# Register.net
KiCad netlist of a schematic drawn in EAGLE
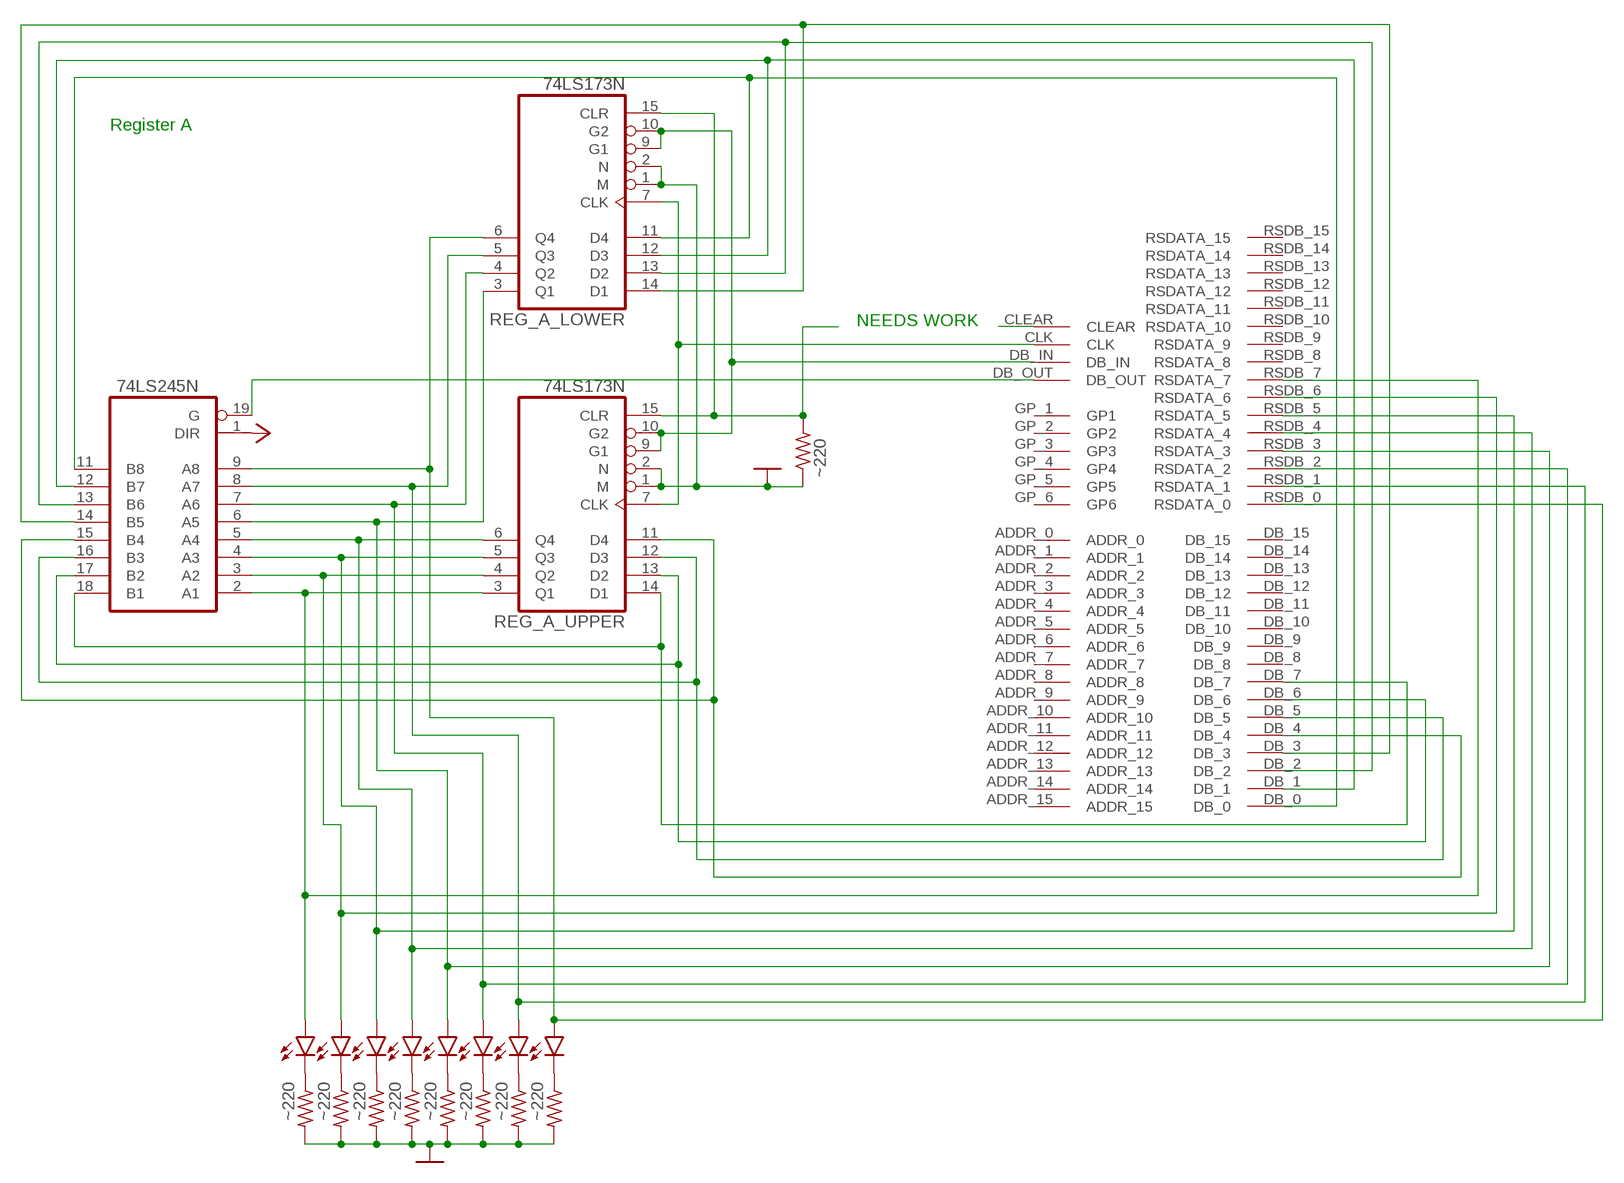
[diagram p0: schematic, sheet 1]

(export (version "E")
  (design (tool "Eeschema 10.0.6"))
  (components
    (comp (ref "LED_A_REG_1")
      (value "LED")
      (footprint "eagle-import:LED5MM")
      (libsource (lib "eagle-import") (part "LED5MM"))
    )
    (comp (ref "LED_A_REG_2")
      (value "LED")
      (footprint "eagle-import:LED5MM")
      (libsource (lib "eagle-import") (part "LED5MM"))
    )
    (comp (ref "LED_A_REG_3")
      (value "LED")
      (footprint "eagle-import:LED5MM")
      (libsource (lib "eagle-import") (part "LED5MM"))
    )
    (comp (ref "LED_A_REG_4")
      (value "LED")
      (footprint "eagle-import:LED5MM")
      (libsource (lib "eagle-import") (part "LED5MM"))
    )
    (comp (ref "LED_A_REG_5")
      (value "LED")
      (footprint "eagle-import:LED5MM")
      (libsource (lib "eagle-import") (part "LED5MM"))
    )
    (comp (ref "LED_A_REG_6")
      (value "LED")
      (footprint "eagle-import:LED5MM")
      (libsource (lib "eagle-import") (part "LED5MM"))
    )
    (comp (ref "LED_A_REG_7")
      (value "LED")
      (footprint "eagle-import:LED5MM")
      (libsource (lib "eagle-import") (part "LED5MM"))
    )
    (comp (ref "LED_A_REG_8")
      (value "LED")
      (footprint "eagle-import:LED5MM")
      (libsource (lib "eagle-import") (part "LED5MM"))
    )
    (comp (ref "OUTPUT_BUFFER_REG_A")
      (value "74LS245N")
      (footprint "eagle-import:DIL20")
      (libsource (lib "eagle-import") (part "74245NLS"))
    )
    (comp (ref "R1")
      (value "~220")
      (footprint "eagle-import:0204_7")
      (libsource (lib "eagle-import") (part "R-US_0204/7"))
    )
    (comp (ref "R2")
      (value "~220")
      (footprint "eagle-import:0204_7")
      (libsource (lib "eagle-import") (part "R-US_0204/7"))
    )
    (comp (ref "R3")
      (value "~220")
      (footprint "eagle-import:0204_7")
      (libsource (lib "eagle-import") (part "R-US_0204/7"))
    )
    (comp (ref "R4")
      (value "~220")
      (footprint "eagle-import:0204_7")
      (libsource (lib "eagle-import") (part "R-US_0204/7"))
    )
    (comp (ref "R5")
      (value "~220")
      (footprint "eagle-import:0204_7")
      (libsource (lib "eagle-import") (part "R-US_0204/7"))
    )
    (comp (ref "R6")
      (value "~220")
      (footprint "eagle-import:0204_7")
      (libsource (lib "eagle-import") (part "R-US_0204/7"))
    )
    (comp (ref "R7")
      (value "~220")
      (footprint "eagle-import:0204_7")
      (libsource (lib "eagle-import") (part "R-US_0204/7"))
    )
    (comp (ref "R8")
      (value "~220")
      (footprint "eagle-import:0204_7")
      (libsource (lib "eagle-import") (part "R-US_0204/7"))
    )
    (comp (ref "R9")
      (value "~220")
      (footprint "eagle-import:0204_7")
      (libsource (lib "eagle-import") (part "R-US_0204/7"))
    )
    (comp (ref "REG_A_LOWER")
      (value "74LS173N")
      (footprint "eagle-import:DIL16")
      (libsource (lib "eagle-import") (part "74173NLS"))
    )
    (comp (ref "REG_A_UPPER")
      (value "74LS173N")
      (footprint "eagle-import:DIL16")
      (libsource (lib "eagle-import") (part "74173NLS"))
    )
    (comp (ref "U$1")
      (value "BACKPLATE_INTERFACE")
      (footprint "eagle-import:BACK_INTERFACE-FOOT")
      (libsource (lib "eagle-import") (part "BACKPLATE_INTERFACE"))
    )
  )
  (nets
    (net (code "1") (name "GND") (class "Default")
      (node (ref "R1") (pin "2") (pinfunction "2_2") (pintype "passive"))
      (node (ref "R2") (pin "2") (pinfunction "2_2") (pintype "passive"))
      (node (ref "R3") (pin "2") (pinfunction "2_2") (pintype "passive"))
      (node (ref "R4") (pin "2") (pinfunction "2_2") (pintype "passive"))
      (node (ref "R5") (pin "2") (pinfunction "2_2") (pintype "passive"))
      (node (ref "R6") (pin "2") (pinfunction "2_2") (pintype "passive"))
      (node (ref "R7") (pin "2") (pinfunction "2_2") (pintype "passive"))
      (node (ref "R8") (pin "2") (pinfunction "2_2") (pintype "passive"))
      (node (ref "R9") (pin "1") (pinfunction "1_1") (pintype "passive"))
      (node (ref "REG_A_LOWER") (pin "1") (pinfunction "M_1") (pintype "input"))
      (node (ref "REG_A_LOWER") (pin "2") (pinfunction "N_2") (pintype "input"))
      (node (ref "REG_A_UPPER") (pin "1") (pinfunction "M_1") (pintype "input"))
      (node (ref "REG_A_UPPER") (pin "2") (pinfunction "N_2") (pintype "input"))
    )
    (net (code "2") (name "Net-(LED_A_REG_1-C)") (class "Default")
      (node (ref "LED_A_REG_1") (pin "K") (pinfunction "C_K") (pintype "passive"))
      (node (ref "R1") (pin "1") (pinfunction "1_1") (pintype "passive"))
    )
    (net (code "3") (name "Net-(LED_A_REG_2-C)") (class "Default")
      (node (ref "LED_A_REG_2") (pin "K") (pinfunction "C_K") (pintype "passive"))
      (node (ref "R2") (pin "1") (pinfunction "1_1") (pintype "passive"))
    )
    (net (code "4") (name "Net-(LED_A_REG_3-C)") (class "Default")
      (node (ref "LED_A_REG_3") (pin "K") (pinfunction "C_K") (pintype "passive"))
      (node (ref "R3") (pin "1") (pinfunction "1_1") (pintype "passive"))
    )
    (net (code "5") (name "Net-(LED_A_REG_4-C)") (class "Default")
      (node (ref "LED_A_REG_4") (pin "K") (pinfunction "C_K") (pintype "passive"))
      (node (ref "R4") (pin "1") (pinfunction "1_1") (pintype "passive"))
    )
    (net (code "6") (name "Net-(LED_A_REG_5-C)") (class "Default")
      (node (ref "LED_A_REG_5") (pin "K") (pinfunction "C_K") (pintype "passive"))
      (node (ref "R5") (pin "1") (pinfunction "1_1") (pintype "passive"))
    )
    (net (code "7") (name "Net-(LED_A_REG_6-C)") (class "Default")
      (node (ref "LED_A_REG_6") (pin "K") (pinfunction "C_K") (pintype "passive"))
      (node (ref "R6") (pin "1") (pinfunction "1_1") (pintype "passive"))
    )
    (net (code "8") (name "Net-(LED_A_REG_7-C)") (class "Default")
      (node (ref "LED_A_REG_7") (pin "K") (pinfunction "C_K") (pintype "passive"))
      (node (ref "R7") (pin "1") (pinfunction "1_1") (pintype "passive"))
    )
    (net (code "9") (name "Net-(LED_A_REG_8-C)") (class "Default")
      (node (ref "LED_A_REG_8") (pin "K") (pinfunction "C_K") (pintype "passive"))
      (node (ref "R8") (pin "1") (pinfunction "1_1") (pintype "passive"))
    )
    (net (code "10") (name "Net-(OUTPUT_BUFFER_REG_AA-A1)") (class "Default")
      (node (ref "LED_A_REG_8") (pin "A") (pinfunction "A_A") (pintype "passive"))
      (node (ref "OUTPUT_BUFFER_REG_A") (pin "2") (pinfunction "A1_2") (pintype "bidirectional"))
      (node (ref "REG_A_UPPER") (pin "3") (pinfunction "Q1_3") (pintype "tri_state"))
      (node (ref "U$1") (pin "RSDB_7") (pinfunction "RSDATA_7_RSDB_7") (pintype "bidirectional"))
    )
    (net (code "11") (name "Net-(OUTPUT_BUFFER_REG_AA-A2)") (class "Default")
      (node (ref "LED_A_REG_7") (pin "A") (pinfunction "A_A") (pintype "passive"))
      (node (ref "OUTPUT_BUFFER_REG_A") (pin "3") (pinfunction "A2_3") (pintype "bidirectional"))
      (node (ref "REG_A_UPPER") (pin "4") (pinfunction "Q2_4") (pintype "tri_state"))
      (node (ref "U$1") (pin "RSDB_6") (pinfunction "RSDATA_6_RSDB_6") (pintype "bidirectional"))
    )
    (net (code "12") (name "Net-(OUTPUT_BUFFER_REG_AA-A3)") (class "Default")
      (node (ref "LED_A_REG_6") (pin "A") (pinfunction "A_A") (pintype "passive"))
      (node (ref "OUTPUT_BUFFER_REG_A") (pin "4") (pinfunction "A3_4") (pintype "bidirectional"))
      (node (ref "REG_A_UPPER") (pin "5") (pinfunction "Q3_5") (pintype "tri_state"))
      (node (ref "U$1") (pin "RSDB_5") (pinfunction "RSDATA_5_RSDB_5") (pintype "bidirectional"))
    )
    (net (code "13") (name "Net-(OUTPUT_BUFFER_REG_AA-A4)") (class "Default")
      (node (ref "LED_A_REG_5") (pin "A") (pinfunction "A_A") (pintype "passive"))
      (node (ref "OUTPUT_BUFFER_REG_A") (pin "5") (pinfunction "A4_5") (pintype "bidirectional"))
      (node (ref "REG_A_UPPER") (pin "6") (pinfunction "Q4_6") (pintype "tri_state"))
      (node (ref "U$1") (pin "RSDB_4") (pinfunction "RSDATA_4_RSDB_4") (pintype "bidirectional"))
    )
    (net (code "14") (name "Net-(OUTPUT_BUFFER_REG_AA-A5)") (class "Default")
      (node (ref "LED_A_REG_4") (pin "A") (pinfunction "A_A") (pintype "passive"))
      (node (ref "OUTPUT_BUFFER_REG_A") (pin "6") (pinfunction "A5_6") (pintype "bidirectional"))
      (node (ref "REG_A_LOWER") (pin "3") (pinfunction "Q1_3") (pintype "tri_state"))
      (node (ref "U$1") (pin "RSDB_3") (pinfunction "RSDATA_3_RSDB_3") (pintype "bidirectional"))
    )
    (net (code "15") (name "Net-(OUTPUT_BUFFER_REG_AA-A6)") (class "Default")
      (node (ref "LED_A_REG_3") (pin "A") (pinfunction "A_A") (pintype "passive"))
      (node (ref "OUTPUT_BUFFER_REG_A") (pin "7") (pinfunction "A6_7") (pintype "bidirectional"))
      (node (ref "REG_A_LOWER") (pin "4") (pinfunction "Q2_4") (pintype "tri_state"))
      (node (ref "U$1") (pin "RSDB_2") (pinfunction "RSDATA_2_RSDB_2") (pintype "bidirectional"))
    )
    (net (code "16") (name "Net-(OUTPUT_BUFFER_REG_AA-A7)") (class "Default")
      (node (ref "LED_A_REG_2") (pin "A") (pinfunction "A_A") (pintype "passive"))
      (node (ref "OUTPUT_BUFFER_REG_A") (pin "8") (pinfunction "A7_8") (pintype "bidirectional"))
      (node (ref "REG_A_LOWER") (pin "5") (pinfunction "Q3_5") (pintype "tri_state"))
      (node (ref "U$1") (pin "RSDB_1") (pinfunction "RSDATA_1_RSDB_1") (pintype "bidirectional"))
    )
    (net (code "17") (name "Net-(OUTPUT_BUFFER_REG_AA-A8)") (class "Default")
      (node (ref "LED_A_REG_1") (pin "A") (pinfunction "A_A") (pintype "passive"))
      (node (ref "OUTPUT_BUFFER_REG_A") (pin "9") (pinfunction "A8_9") (pintype "bidirectional"))
      (node (ref "REG_A_LOWER") (pin "6") (pinfunction "Q4_6") (pintype "tri_state"))
      (node (ref "U$1") (pin "RSDB_0") (pinfunction "RSDATA_0_RSDB_0") (pintype "bidirectional"))
    )
    (net (code "18") (name "Net-(OUTPUT_BUFFER_REG_AA-B1)") (class "Default")
      (node (ref "OUTPUT_BUFFER_REG_A") (pin "18") (pinfunction "B1_18") (pintype "bidirectional"))
      (node (ref "REG_A_UPPER") (pin "14") (pinfunction "D1_14") (pintype "input"))
      (node (ref "U$1") (pin "DB_7") (pinfunction "DB_7_DB_7") (pintype "bidirectional"))
    )
    (net (code "19") (name "Net-(OUTPUT_BUFFER_REG_AA-B2)") (class "Default")
      (node (ref "OUTPUT_BUFFER_REG_A") (pin "17") (pinfunction "B2_17") (pintype "bidirectional"))
      (node (ref "REG_A_UPPER") (pin "13") (pinfunction "D2_13") (pintype "input"))
      (node (ref "U$1") (pin "DB_6") (pinfunction "DB_6_DB_6") (pintype "bidirectional"))
    )
    (net (code "20") (name "Net-(OUTPUT_BUFFER_REG_AA-B3)") (class "Default")
      (node (ref "OUTPUT_BUFFER_REG_A") (pin "16") (pinfunction "B3_16") (pintype "bidirectional"))
      (node (ref "REG_A_UPPER") (pin "12") (pinfunction "D3_12") (pintype "input"))
      (node (ref "U$1") (pin "DB_5") (pinfunction "DB_5_DB_5") (pintype "bidirectional"))
    )
    (net (code "21") (name "Net-(OUTPUT_BUFFER_REG_AA-B4)") (class "Default")
      (node (ref "OUTPUT_BUFFER_REG_A") (pin "15") (pinfunction "B4_15") (pintype "bidirectional"))
      (node (ref "REG_A_UPPER") (pin "11") (pinfunction "D4_11") (pintype "input"))
      (node (ref "U$1") (pin "DB_4") (pinfunction "DB_4_DB_4") (pintype "bidirectional"))
    )
    (net (code "22") (name "Net-(OUTPUT_BUFFER_REG_AA-B5)") (class "Default")
      (node (ref "OUTPUT_BUFFER_REG_A") (pin "14") (pinfunction "B5_14") (pintype "bidirectional"))
      (node (ref "REG_A_LOWER") (pin "14") (pinfunction "D1_14") (pintype "input"))
      (node (ref "U$1") (pin "DB_3") (pinfunction "DB_3_DB_3") (pintype "bidirectional"))
    )
    (net (code "23") (name "Net-(OUTPUT_BUFFER_REG_AA-B6)") (class "Default")
      (node (ref "OUTPUT_BUFFER_REG_A") (pin "13") (pinfunction "B6_13") (pintype "bidirectional"))
      (node (ref "REG_A_LOWER") (pin "13") (pinfunction "D2_13") (pintype "input"))
      (node (ref "U$1") (pin "DB_2") (pinfunction "DB_2_DB_2") (pintype "bidirectional"))
    )
    (net (code "24") (name "Net-(OUTPUT_BUFFER_REG_AA-B7)") (class "Default")
      (node (ref "OUTPUT_BUFFER_REG_A") (pin "12") (pinfunction "B7_12") (pintype "bidirectional"))
      (node (ref "REG_A_LOWER") (pin "12") (pinfunction "D3_12") (pintype "input"))
      (node (ref "U$1") (pin "DB_1") (pinfunction "DB_1_DB_1") (pintype "bidirectional"))
    )
    (net (code "25") (name "Net-(OUTPUT_BUFFER_REG_AA-B8)") (class "Default")
      (node (ref "OUTPUT_BUFFER_REG_A") (pin "11") (pinfunction "B8_11") (pintype "bidirectional"))
      (node (ref "REG_A_LOWER") (pin "11") (pinfunction "D4_11") (pintype "input"))
      (node (ref "U$1") (pin "DB_0") (pinfunction "DB_0_DB_0") (pintype "bidirectional"))
    )
    (net (code "26") (name "Net-(OUTPUT_BUFFER_REG_AA-G)") (class "Default")
      (node (ref "OUTPUT_BUFFER_REG_A") (pin "19") (pinfunction "G_19") (pintype "input"))
      (node (ref "U$1") (pin "DB_OUT") (pinfunction "DB_OUT_DB_OUT") (pintype "bidirectional"))
    )
    (net (code "27") (name "Net-(REG_A_LOWERA-CLK)") (class "Default")
      (node (ref "REG_A_LOWER") (pin "7") (pinfunction "CLK_7") (pintype "input"))
      (node (ref "REG_A_UPPER") (pin "7") (pinfunction "CLK_7") (pintype "input"))
      (node (ref "U$1") (pin "CLK") (pinfunction "CLK_CLK") (pintype "bidirectional"))
    )
    (net (code "28") (name "Net-(REG_A_LOWERA-CLR)") (class "Default")
      (node (ref "R9") (pin "2") (pinfunction "2_2") (pintype "passive"))
      (node (ref "REG_A_LOWER") (pin "15") (pinfunction "CLR_15") (pintype "input"))
      (node (ref "REG_A_UPPER") (pin "15") (pinfunction "CLR_15") (pintype "input"))
    )
    (net (code "29") (name "Net-(REG_A_LOWERA-G1)") (class "Default")
      (node (ref "REG_A_LOWER") (pin "10") (pinfunction "G2_10") (pintype "input"))
      (node (ref "REG_A_LOWER") (pin "9") (pinfunction "G1_9") (pintype "input"))
      (node (ref "REG_A_UPPER") (pin "10") (pinfunction "G2_10") (pintype "input"))
      (node (ref "REG_A_UPPER") (pin "9") (pinfunction "G1_9") (pintype "input"))
      (node (ref "U$1") (pin "DB_IN") (pinfunction "DB_IN_DB_IN") (pintype "bidirectional"))
    )
    (net (code "30") (name "VCC") (class "Default")
      (node (ref "OUTPUT_BUFFER_REG_A") (pin "1") (pinfunction "DIR_1") (pintype "input"))
    )
    (net (code "31") (name "unconnected-(U$1-PadADDR_0)") (class "Default")
      (node (ref "U$1") (pin "ADDR_0") (pinfunction "ADDR_0_ADDR_0") (pintype "bidirectional"))
    )
    (net (code "32") (name "unconnected-(U$1-PadADDR_1)") (class "Default")
      (node (ref "U$1") (pin "ADDR_1") (pinfunction "ADDR_1_ADDR_1") (pintype "bidirectional"))
    )
    (net (code "33") (name "unconnected-(U$1-PadADDR_2)") (class "Default")
      (node (ref "U$1") (pin "ADDR_2") (pinfunction "ADDR_2_ADDR_2") (pintype "bidirectional"))
    )
    (net (code "34") (name "unconnected-(U$1-PadADDR_3)") (class "Default")
      (node (ref "U$1") (pin "ADDR_3") (pinfunction "ADDR_3_ADDR_3") (pintype "bidirectional"))
    )
    (net (code "35") (name "unconnected-(U$1-PadADDR_4)") (class "Default")
      (node (ref "U$1") (pin "ADDR_4") (pinfunction "ADDR_4_ADDR_4") (pintype "bidirectional"))
    )
    (net (code "36") (name "unconnected-(U$1-PadADDR_5)") (class "Default")
      (node (ref "U$1") (pin "ADDR_5") (pinfunction "ADDR_5_ADDR_5") (pintype "bidirectional"))
    )
    (net (code "37") (name "unconnected-(U$1-PadADDR_6)") (class "Default")
      (node (ref "U$1") (pin "ADDR_6") (pinfunction "ADDR_6_ADDR_6") (pintype "bidirectional"))
    )
    (net (code "38") (name "unconnected-(U$1-PadADDR_7)") (class "Default")
      (node (ref "U$1") (pin "ADDR_7") (pinfunction "ADDR_7_ADDR_7") (pintype "bidirectional"))
    )
    (net (code "39") (name "unconnected-(U$1-PadADDR_8)") (class "Default")
      (node (ref "U$1") (pin "ADDR_8") (pinfunction "ADDR_8_ADDR_8") (pintype "bidirectional"))
    )
    (net (code "40") (name "unconnected-(U$1-PadADDR_9)") (class "Default")
      (node (ref "U$1") (pin "ADDR_9") (pinfunction "ADDR_9_ADDR_9") (pintype "bidirectional"))
    )
    (net (code "41") (name "unconnected-(U$1-PadADDR_10)") (class "Default")
      (node (ref "U$1") (pin "ADDR_10") (pinfunction "ADDR_10_ADDR_10") (pintype "bidirectional"))
    )
    (net (code "42") (name "unconnected-(U$1-PadADDR_11)") (class "Default")
      (node (ref "U$1") (pin "ADDR_11") (pinfunction "ADDR_11_ADDR_11") (pintype "bidirectional"))
    )
    (net (code "43") (name "unconnected-(U$1-PadADDR_12)") (class "Default")
      (node (ref "U$1") (pin "ADDR_12") (pinfunction "ADDR_12_ADDR_12") (pintype "bidirectional"))
    )
    (net (code "44") (name "unconnected-(U$1-PadADDR_13)") (class "Default")
      (node (ref "U$1") (pin "ADDR_13") (pinfunction "ADDR_13_ADDR_13") (pintype "bidirectional"))
    )
    (net (code "45") (name "unconnected-(U$1-PadADDR_14)") (class "Default")
      (node (ref "U$1") (pin "ADDR_14") (pinfunction "ADDR_14_ADDR_14") (pintype "bidirectional"))
    )
    (net (code "46") (name "unconnected-(U$1-PadADDR_15)") (class "Default")
      (node (ref "U$1") (pin "ADDR_15") (pinfunction "ADDR_15_ADDR_15") (pintype "bidirectional"))
    )
    (net (code "47") (name "unconnected-(U$1-PadCLEAR)") (class "Default")
      (node (ref "U$1") (pin "CLEAR") (pinfunction "CLEAR_CLEAR") (pintype "bidirectional"))
    )
    (net (code "48") (name "unconnected-(U$1-PadDB_8)") (class "Default")
      (node (ref "U$1") (pin "DB_8") (pinfunction "DB_8_DB_8") (pintype "bidirectional"))
    )
    (net (code "49") (name "unconnected-(U$1-PadDB_9)") (class "Default")
      (node (ref "U$1") (pin "DB_9") (pinfunction "DB_9_DB_9") (pintype "bidirectional"))
    )
    (net (code "50") (name "unconnected-(U$1-PadDB_10)") (class "Default")
      (node (ref "U$1") (pin "DB_10") (pinfunction "DB_10_DB_10") (pintype "bidirectional"))
    )
    (net (code "51") (name "unconnected-(U$1-PadDB_11)") (class "Default")
      (node (ref "U$1") (pin "DB_11") (pinfunction "DB_11_DB_11") (pintype "bidirectional"))
    )
    (net (code "52") (name "unconnected-(U$1-PadDB_12)") (class "Default")
      (node (ref "U$1") (pin "DB_12") (pinfunction "DB_12_DB_12") (pintype "bidirectional"))
    )
    (net (code "53") (name "unconnected-(U$1-PadDB_13)") (class "Default")
      (node (ref "U$1") (pin "DB_13") (pinfunction "DB_13_DB_13") (pintype "bidirectional"))
    )
    (net (code "54") (name "unconnected-(U$1-PadDB_14)") (class "Default")
      (node (ref "U$1") (pin "DB_14") (pinfunction "DB_14_DB_14") (pintype "bidirectional"))
    )
    (net (code "55") (name "unconnected-(U$1-PadDB_15)") (class "Default")
      (node (ref "U$1") (pin "DB_15") (pinfunction "DB_15_DB_15") (pintype "bidirectional"))
    )
    (net (code "56") (name "unconnected-(U$1A-GP1-PadGP_1)") (class "Default")
      (node (ref "U$1") (pin "GP_1") (pinfunction "GP1_GP_1") (pintype "bidirectional"))
    )
    (net (code "57") (name "unconnected-(U$1A-GP2-PadGP_2)") (class "Default")
      (node (ref "U$1") (pin "GP_2") (pinfunction "GP2_GP_2") (pintype "bidirectional"))
    )
    (net (code "58") (name "unconnected-(U$1A-GP3-PadGP_3)") (class "Default")
      (node (ref "U$1") (pin "GP_3") (pinfunction "GP3_GP_3") (pintype "bidirectional"))
    )
    (net (code "59") (name "unconnected-(U$1A-GP4-PadGP_4)") (class "Default")
      (node (ref "U$1") (pin "GP_4") (pinfunction "GP4_GP_4") (pintype "bidirectional"))
    )
    (net (code "60") (name "unconnected-(U$1A-GP5-PadGP_5)") (class "Default")
      (node (ref "U$1") (pin "GP_5") (pinfunction "GP5_GP_5") (pintype "bidirectional"))
    )
    (net (code "61") (name "unconnected-(U$1A-GP6-PadGP_6)") (class "Default")
      (node (ref "U$1") (pin "GP_6") (pinfunction "GP6_GP_6") (pintype "bidirectional"))
    )
    (net (code "62") (name "unconnected-(U$1A-RSDATA_8-PadRSDB_8)") (class "Default")
      (node (ref "U$1") (pin "RSDB_8") (pinfunction "RSDATA_8_RSDB_8") (pintype "bidirectional"))
    )
    (net (code "63") (name "unconnected-(U$1A-RSDATA_9-PadRSDB_9)") (class "Default")
      (node (ref "U$1") (pin "RSDB_9") (pinfunction "RSDATA_9_RSDB_9") (pintype "bidirectional"))
    )
    (net (code "64") (name "unconnected-(U$1A-RSDATA_10-PadRSDB_10)") (class "Default")
      (node (ref "U$1") (pin "RSDB_10") (pinfunction "RSDATA_10_RSDB_10") (pintype "bidirectional"))
    )
    (net (code "65") (name "unconnected-(U$1A-RSDATA_11-PadRSDB_11)") (class "Default")
      (node (ref "U$1") (pin "RSDB_11") (pinfunction "RSDATA_11_RSDB_11") (pintype "bidirectional"))
    )
    (net (code "66") (name "unconnected-(U$1A-RSDATA_12-PadRSDB_12)") (class "Default")
      (node (ref "U$1") (pin "RSDB_12") (pinfunction "RSDATA_12_RSDB_12") (pintype "bidirectional"))
    )
    (net (code "67") (name "unconnected-(U$1A-RSDATA_13-PadRSDB_13)") (class "Default")
      (node (ref "U$1") (pin "RSDB_13") (pinfunction "RSDATA_13_RSDB_13") (pintype "bidirectional"))
    )
    (net (code "68") (name "unconnected-(U$1A-RSDATA_14-PadRSDB_14)") (class "Default")
      (node (ref "U$1") (pin "RSDB_14") (pinfunction "RSDATA_14_RSDB_14") (pintype "bidirectional"))
    )
    (net (code "69") (name "unconnected-(U$1A-RSDATA_15-PadRSDB_15)") (class "Default")
      (node (ref "U$1") (pin "RSDB_15") (pinfunction "RSDATA_15_RSDB_15") (pintype "bidirectional"))
    )
  )
)
